# B_PCB1.net
KiCad netlist of a schematic drawn in EAGLE
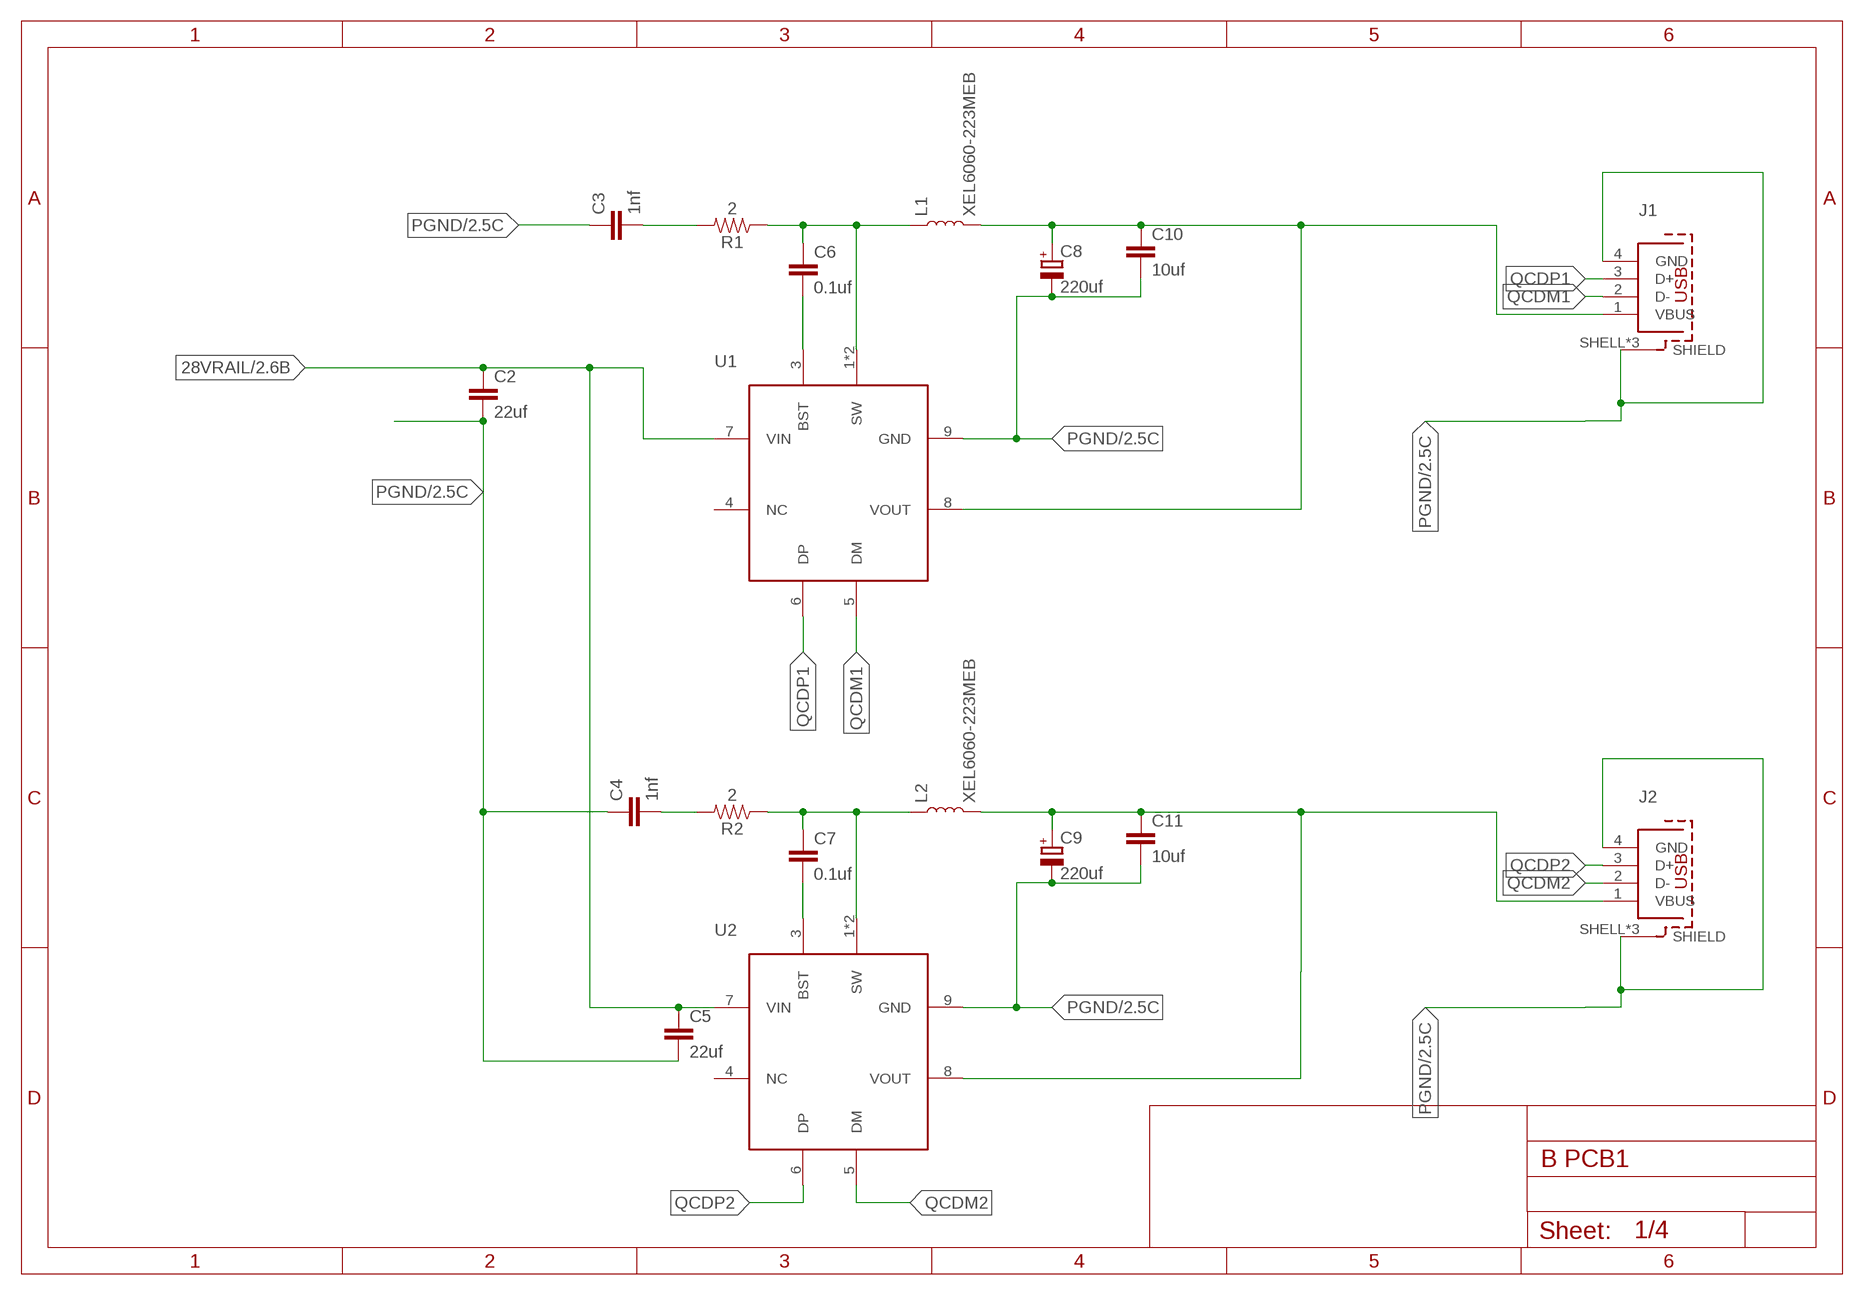
[diagram p0: schematic, sheet 1]
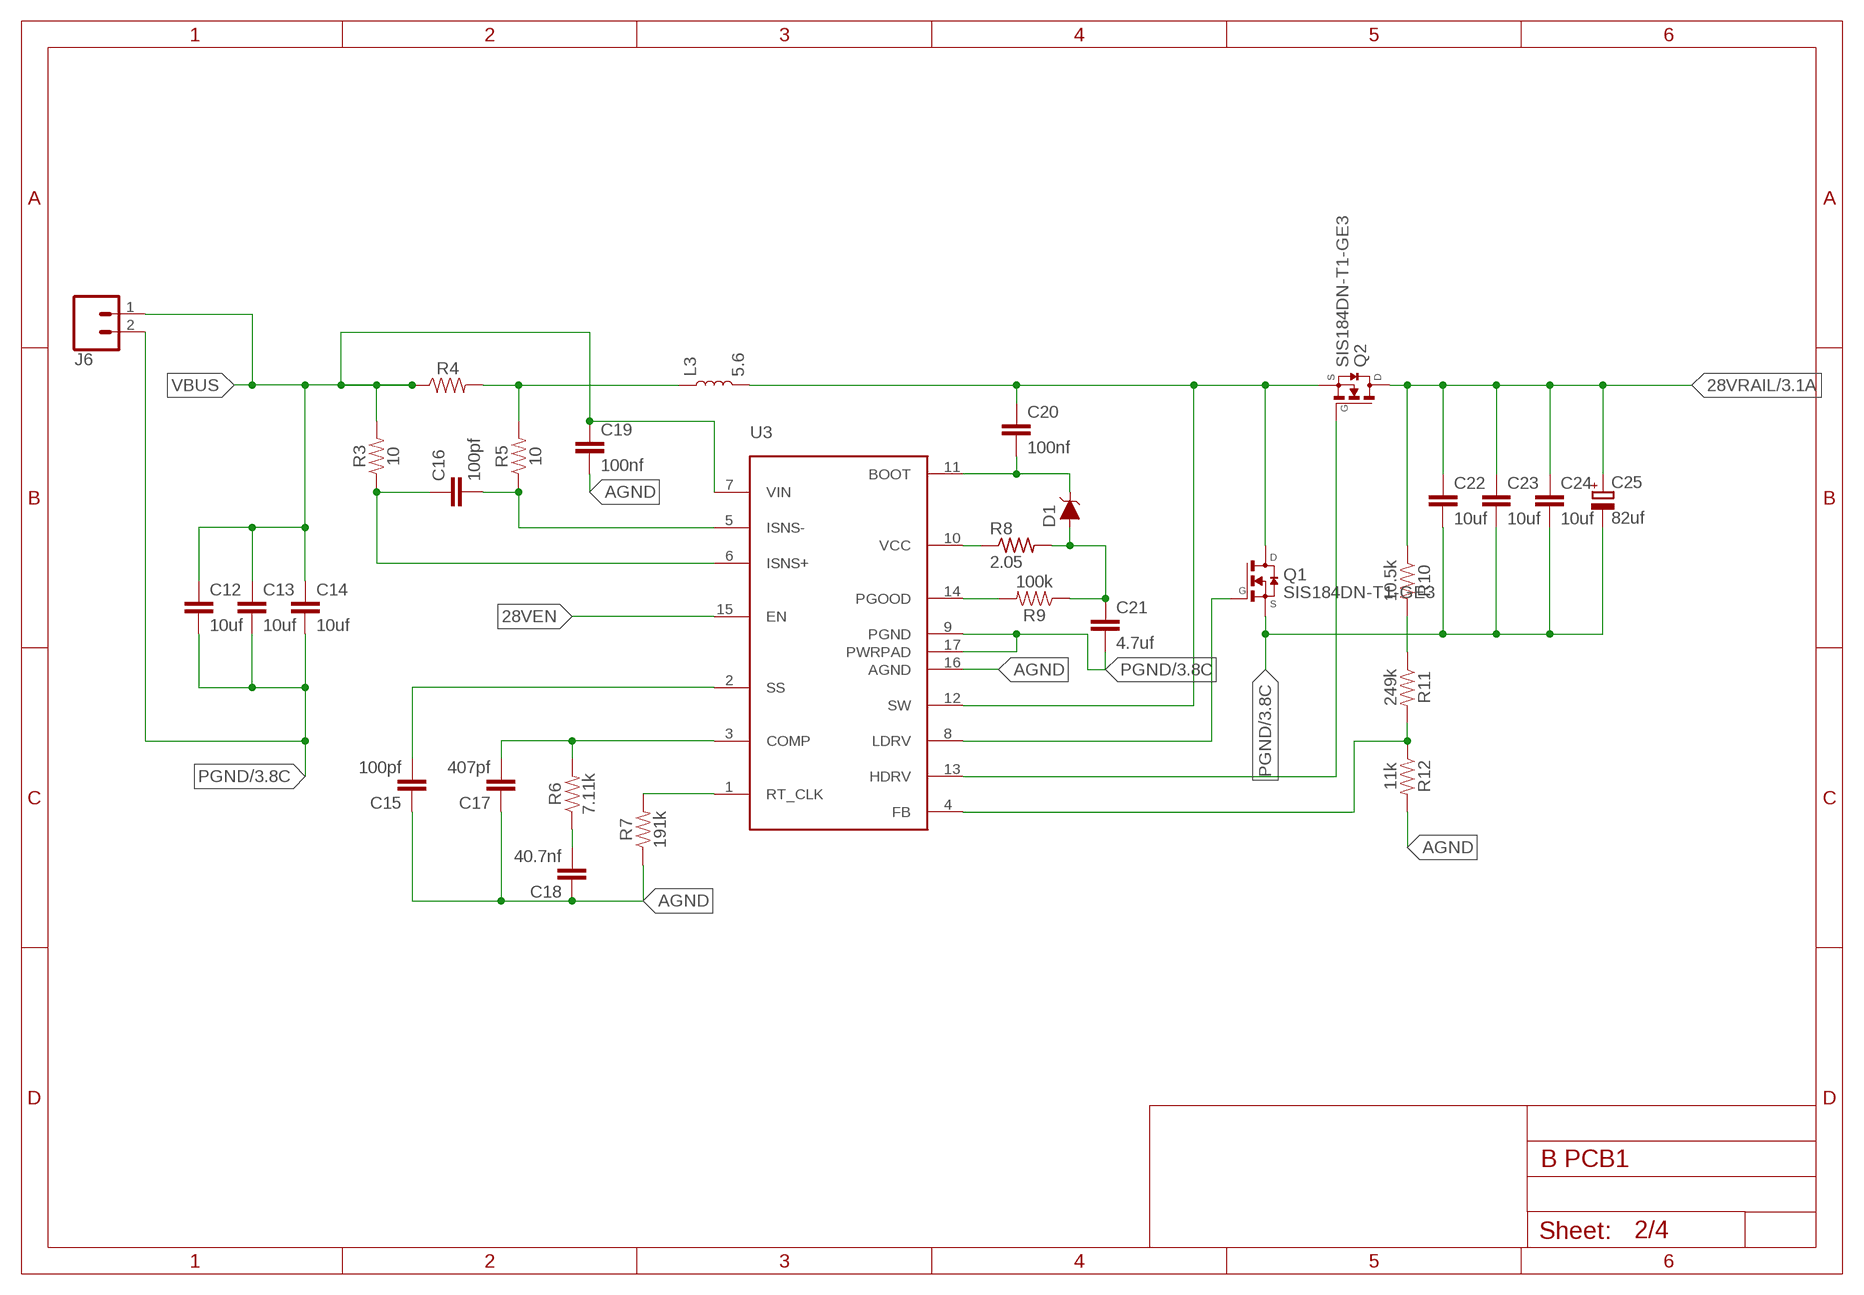
[diagram p1: schematic, sheet 2]
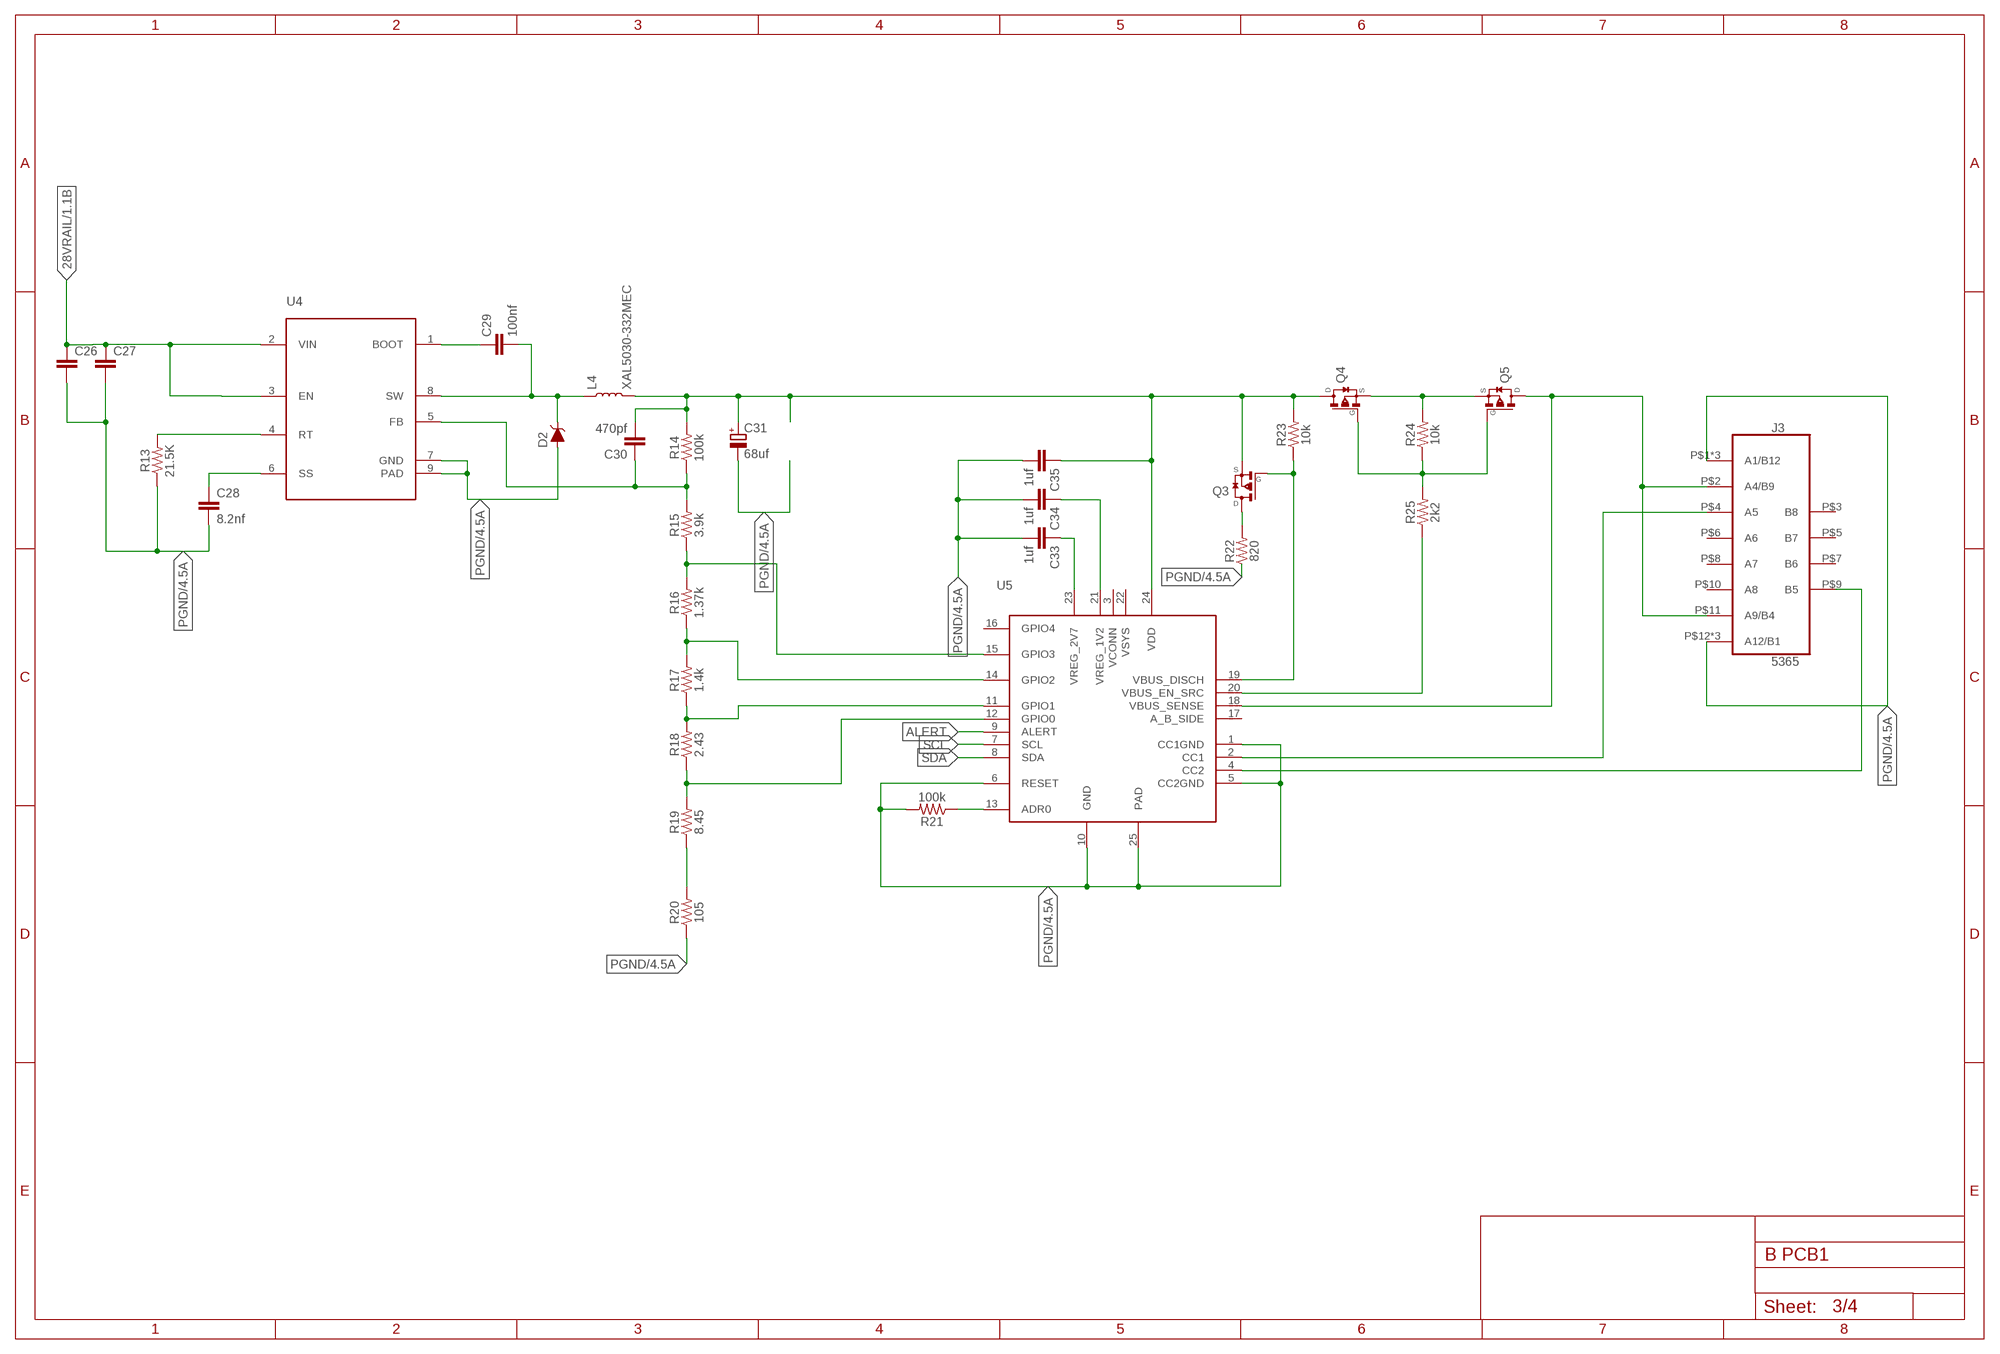
[diagram p2: schematic, sheet 3]
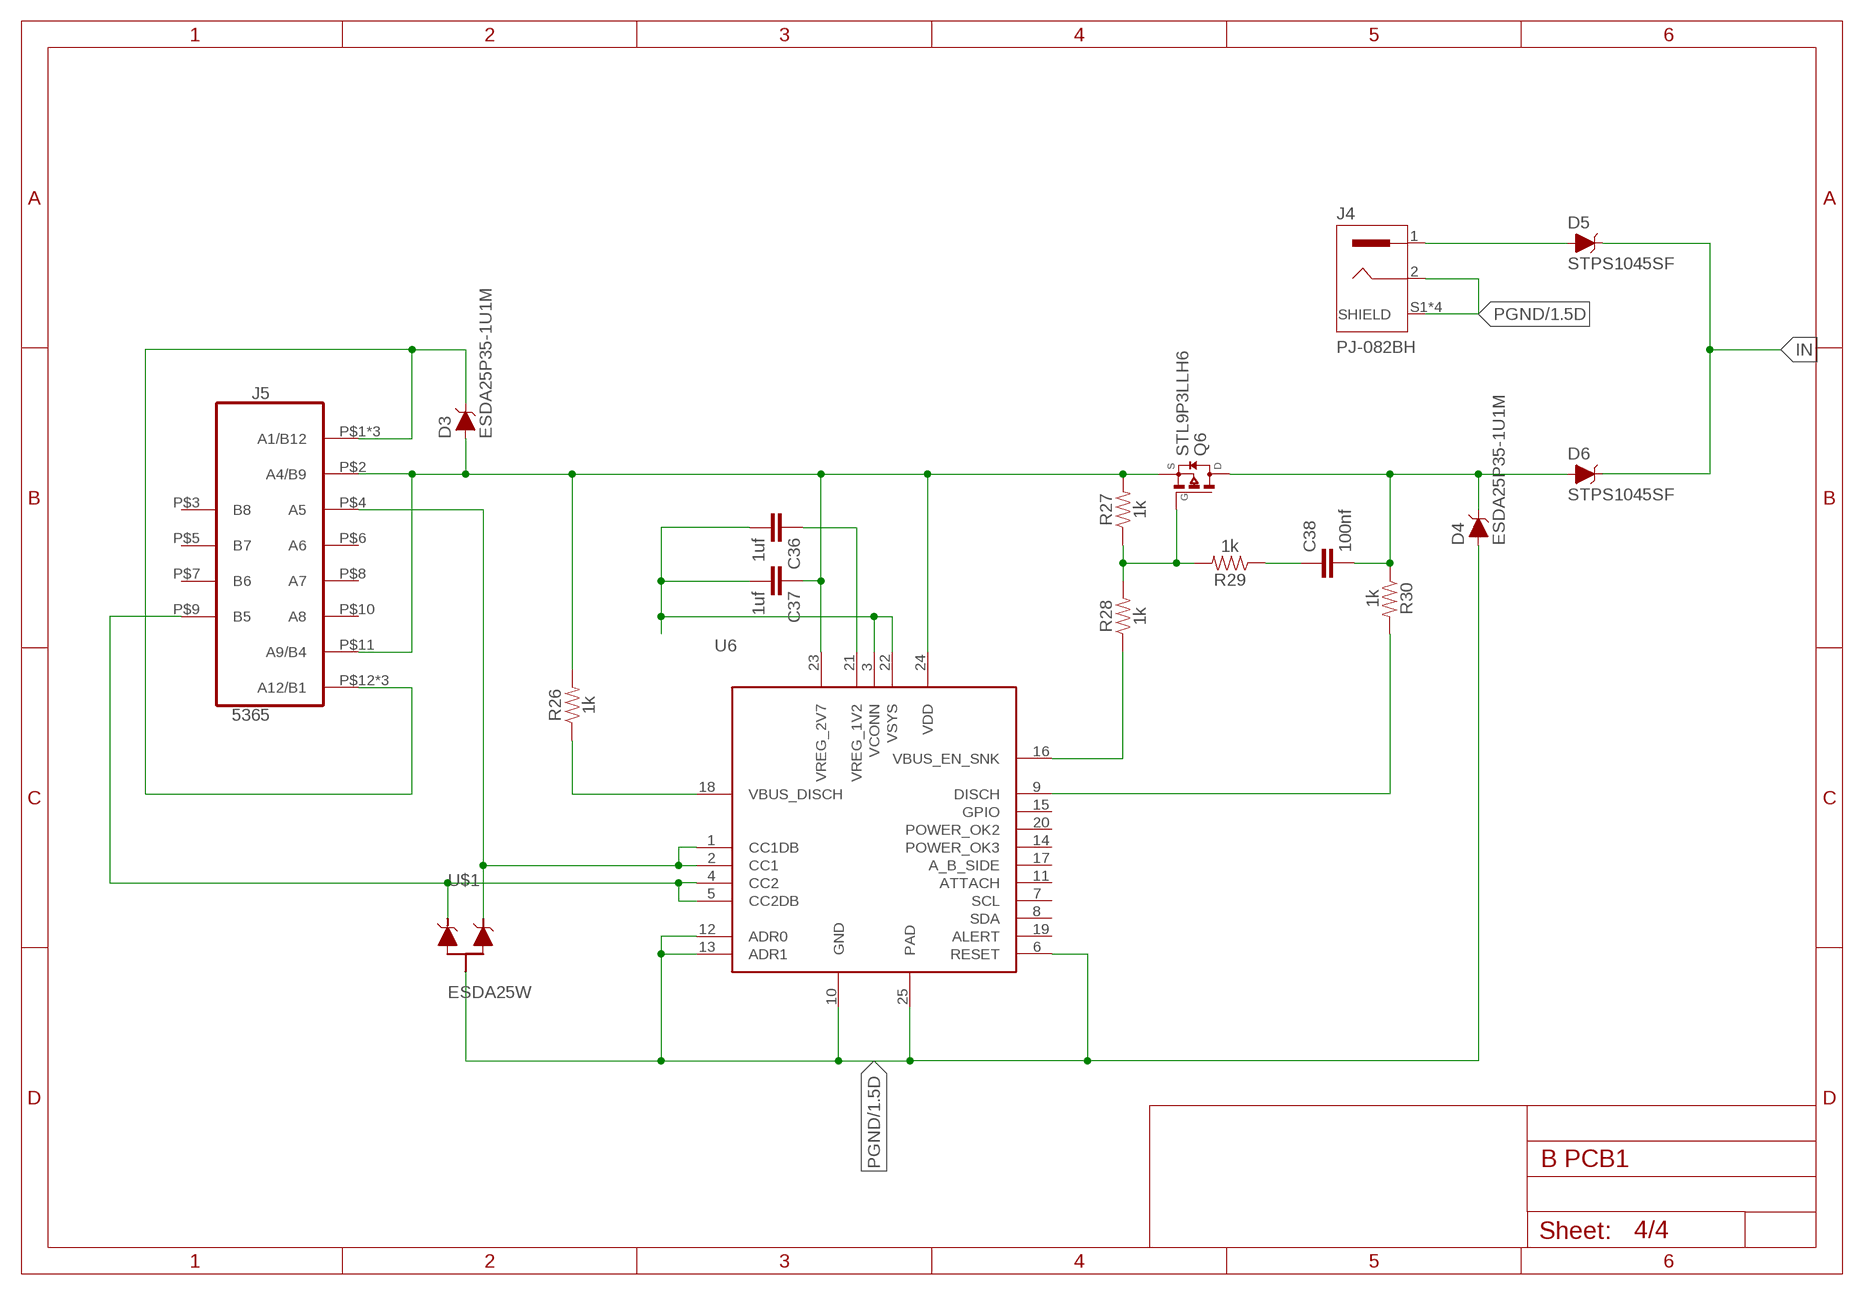
[diagram p3: schematic, sheet 4]

(export (version "E")
  (design (tool "Eeschema 10.0.6"))
  (components
    (comp (ref "C12")
      (value "10uf")
      (footprint "eagle-import:C0805K")
      (libsource (lib "eagle-import") (part "C-EUC0805K"))
    )
    (comp (ref "C13")
      (value "10uf")
      (footprint "eagle-import:C0805K")
      (libsource (lib "eagle-import") (part "C-EUC0805K"))
    )
    (comp (ref "C14")
      (value "10uf")
      (footprint "eagle-import:C0805K")
      (libsource (lib "eagle-import") (part "C-EUC0805K"))
    )
    (comp (ref "C15")
      (value "100pf")
      (footprint "eagle-import:C0402K")
      (libsource (lib "eagle-import") (part "C-EUC0402K"))
    )
    (comp (ref "C16")
      (value "100pf")
      (footprint "eagle-import:C0402K")
      (libsource (lib "eagle-import") (part "C-EUC0402K"))
    )
    (comp (ref "C17")
      (value "407pf")
      (footprint "eagle-import:C0402K")
      (libsource (lib "eagle-import") (part "C-EUC0402K"))
    )
    (comp (ref "C18")
      (value "40.7nf")
      (footprint "eagle-import:C0402K")
      (libsource (lib "eagle-import") (part "C-EUC0402K"))
    )
    (comp (ref "C19")
      (value "100nf")
      (footprint "eagle-import:C0402K")
      (libsource (lib "eagle-import") (part "C-EUC0402K"))
    )
    (comp (ref "C20")
      (value "100nf")
      (footprint "eagle-import:C0402K")
      (libsource (lib "eagle-import") (part "C-EUC0402K"))
    )
    (comp (ref "C21")
      (value "4.7uf")
      (footprint "eagle-import:C0402K")
      (libsource (lib "eagle-import") (part "C-EUC0402K"))
    )
    (comp (ref "C22")
      (value "10uf")
      (footprint "eagle-import:C1206K")
      (libsource (lib "eagle-import") (part "C-EUC1206K"))
    )
    (comp (ref "C23")
      (value "10uf")
      (footprint "eagle-import:C1206K")
      (libsource (lib "eagle-import") (part "C-EUC1206K"))
    )
    (comp (ref "C24")
      (value "10uf")
      (footprint "eagle-import:C1206K")
      (libsource (lib "eagle-import") (part "C-EUC1206K"))
    )
    (comp (ref "C25")
      (value "82uf")
      (footprint "eagle-import:CAPAE660X800")
      (libsource (lib "eagle-import") (part "EMZR250ARA221MF80G"))
    )
    (comp (ref "D1")
      (value "SS24FL")
      (footprint "eagle-import:SODFL3617X108")
      (libsource (lib "eagle-import") (part "SS24FL"))
    )
    (comp (ref "J6")
      (value "CONN_021.4HOLE")
      (footprint "eagle-import:1X02_1.4HOLE")
      (libsource (lib "eagle-import") (part "CONN_021.4HOLE"))
    )
    (comp (ref "L3")
      (value "5.6")
      (footprint "eagle-import:RESM7275X700")
      (libsource (lib "eagle-import") (part "XAL7070-472MEB"))
    )
    (comp (ref "Q1")
      (value "SIS184DN-T1-GE3")
      (footprint "eagle-import:SIS184DN-T1-GE3")
      (libsource (lib "eagle-import") (part "SIS184DN-T1-GE3"))
    )
    (comp (ref "Q2")
      (value "SIS184DN-T1-GE3")
      (footprint "eagle-import:SIS184DN-T1-GE3")
      (libsource (lib "eagle-import") (part "SIS184DN-T1-GE3"))
    )
    (comp (ref "R3")
      (value "10")
      (footprint "eagle-import:0402")
      (libsource (lib "eagle-import") (part "RES4K04020402"))
    )
    (comp (ref "R4")
      (value "LRMAM2512-R0035FT4")
      (footprint "eagle-import:RESC6432X90")
      (libsource (lib "eagle-import") (part "LRMAM2512-R0035FT4"))
    )
    (comp (ref "R5")
      (value "10")
      (footprint "eagle-import:0402")
      (libsource (lib "eagle-import") (part "RES4K04020402"))
    )
    (comp (ref "R6")
      (value "7.11k")
      (footprint "eagle-import:0402")
      (libsource (lib "eagle-import") (part "RES4K04020402"))
    )
    (comp (ref "R7")
      (value "191k")
      (footprint "eagle-import:0402")
      (libsource (lib "eagle-import") (part "RES4K04020402"))
    )
    (comp (ref "R8")
      (value "2.05")
      (footprint "eagle-import:R0603")
      (libsource (lib "eagle-import") (part "R-US_R0603"))
    )
    (comp (ref "R9")
      (value "100k")
      (footprint "eagle-import:0402")
      (libsource (lib "eagle-import") (part "RES4K04020402"))
    )
    (comp (ref "R10")
      (value "10.5k")
      (footprint "eagle-import:0402")
      (libsource (lib "eagle-import") (part "RES4K04020402"))
    )
    (comp (ref "R11")
      (value "249k")
      (footprint "eagle-import:0402")
      (libsource (lib "eagle-import") (part "RES4K04020402"))
    )
    (comp (ref "R12")
      (value "11k")
      (footprint "eagle-import:0402")
      (libsource (lib "eagle-import") (part "RES4K04020402"))
    )
    (comp (ref "U3")
      (value "TPS43061")
      (footprint "eagle-import:QFN50P300X300X100-17T80X120")
      (libsource (lib "eagle-import") (part "TPS43061"))
    )
    (comp (ref "C26")
      (value "C-EUC1210")
      (footprint "eagle-import:C1210")
      (libsource (lib "eagle-import") (part "C-EUC1210"))
    )
    (comp (ref "C27")
      (value "C-EUC1210")
      (footprint "eagle-import:C1210")
      (libsource (lib "eagle-import") (part "C-EUC1210"))
    )
    (comp (ref "C28")
      (value "8.2nf")
      (footprint "eagle-import:C0402K")
      (libsource (lib "eagle-import") (part "C-EUC0402K"))
    )
    (comp (ref "C29")
      (value "100nf")
      (footprint "eagle-import:C0402K")
      (libsource (lib "eagle-import") (part "C-EUC0402K"))
    )
    (comp (ref "C30")
      (value "470pf")
      (footprint "eagle-import:C0402K")
      (libsource (lib "eagle-import") (part "C-EUC0402K"))
    )
    (comp (ref "C31")
      (value "68uf")
      (footprint "eagle-import:CAPAE830X1040")
      (libsource (lib "eagle-import") (part "PCR1H820MCL6GS"))
    )
    (comp (ref "C33")
      (value "1uf")
      (footprint "eagle-import:C0402K")
      (libsource (lib "eagle-import") (part "C-EUC0402K"))
    )
    (comp (ref "C34")
      (value "1uf")
      (footprint "eagle-import:C0402K")
      (libsource (lib "eagle-import") (part "C-EUC0402K"))
    )
    (comp (ref "C35")
      (value "1uf")
      (footprint "eagle-import:C0402K")
      (libsource (lib "eagle-import") (part "C-EUC0402K"))
    )
    (comp (ref "D2")
      (value "B560C-13-F")
      (footprint "eagle-import:DIOM6859X250")
      (libsource (lib "eagle-import") (part "B560C-13-F"))
    )
    (comp (ref "J3")
      (value "5365")
      (footprint "eagle-import:5365")
      (libsource (lib "eagle-import") (part "5365"))
    )
    (comp (ref "L4")
      (value "XAL5030-332MEC")
      (footprint "eagle-import:INDM5355X310")
      (libsource (lib "eagle-import") (part "XAL5030-332MEC"))
    )
    (comp (ref "Q3")
      (value "STR2P3LLH6")
      (footprint "eagle-import:SOT95P280X125-3")
      (libsource (lib "eagle-import") (part "STR2P3LLH6"))
    )
    (comp (ref "Q4")
      (value "STL9P3LLH6")
      (footprint "eagle-import:SON65P330X330X80-8")
      (libsource (lib "eagle-import") (part "STL9P3LLH6"))
    )
    (comp (ref "Q5")
      (value "STL9P3LLH6")
      (footprint "eagle-import:SON65P330X330X80-8")
      (libsource (lib "eagle-import") (part "STL9P3LLH6"))
    )
    (comp (ref "R13")
      (value "21.5K")
      (footprint "eagle-import:0402")
      (libsource (lib "eagle-import") (part "RES4K04020402"))
    )
    (comp (ref "R14")
      (value "100k")
      (footprint "eagle-import:0402")
      (libsource (lib "eagle-import") (part "RES4K04020402"))
    )
    (comp (ref "R15")
      (value "3.9k")
      (footprint "eagle-import:0402")
      (libsource (lib "eagle-import") (part "RES4K04020402"))
    )
    (comp (ref "R16")
      (value "1.37k")
      (footprint "eagle-import:0402")
      (libsource (lib "eagle-import") (part "RES4K04020402"))
    )
    (comp (ref "R17")
      (value "1.4k")
      (footprint "eagle-import:0402")
      (libsource (lib "eagle-import") (part "RES4K04020402"))
    )
    (comp (ref "R18")
      (value "2.43")
      (footprint "eagle-import:0402")
      (libsource (lib "eagle-import") (part "RES4K04020402"))
    )
    (comp (ref "R19")
      (value "8.45")
      (footprint "eagle-import:0402")
      (libsource (lib "eagle-import") (part "RES4K04020402"))
    )
    (comp (ref "R20")
      (value "105")
      (footprint "eagle-import:0402")
      (libsource (lib "eagle-import") (part "RES4K04020402"))
    )
    (comp (ref "R21")
      (value "100k")
      (footprint "eagle-import:0402")
      (fields (field (name "SPICEPREFIX") "R"))
      (libsource (lib "eagle-import") (part "RES4K04020402"))
    )
    (comp (ref "R22")
      (value "820")
      (footprint "eagle-import:0402")
      (libsource (lib "eagle-import") (part "RES4K04020402"))
    )
    (comp (ref "R23")
      (value "10k")
      (footprint "eagle-import:0402")
      (libsource (lib "eagle-import") (part "RES4K04020402"))
    )
    (comp (ref "R24")
      (value "10k")
      (footprint "eagle-import:0402")
      (libsource (lib "eagle-import") (part "RES4K04020402"))
    )
    (comp (ref "R25")
      (value "2k2")
      (footprint "eagle-import:0402")
      (libsource (lib "eagle-import") (part "RES4K04020402"))
    )
    (comp (ref "U4")
      (value "LMR14050")
      (footprint "eagle-import:SOIC127P600X170-9T240X260")
      (libsource (lib "eagle-import") (part "LMR14050"))
    )
    (comp (ref "U5")
      (value "STUSB4700")
      (footprint "eagle-import:QFN50P400X400X100-25T270")
      (libsource (lib "eagle-import") (part "STUSB4700"))
    )
    (comp (ref "C2")
      (value "22uf")
      (footprint "eagle-import:C0805K")
      (libsource (lib "eagle-import") (part "C-EUC0805K"))
    )
    (comp (ref "C3")
      (value "1nf")
      (footprint "eagle-import:C0402K")
      (libsource (lib "eagle-import") (part "C-EUC0402K"))
    )
    (comp (ref "C4")
      (value "1nf")
      (footprint "eagle-import:C0402K")
      (libsource (lib "eagle-import") (part "C-EUC0402K"))
    )
    (comp (ref "C5")
      (value "22uf")
      (footprint "eagle-import:C0805K")
      (libsource (lib "eagle-import") (part "C-EUC0805K"))
    )
    (comp (ref "C6")
      (value "0.1uf")
      (footprint "eagle-import:C0805K")
      (libsource (lib "eagle-import") (part "C-EUC0805K"))
    )
    (comp (ref "C7")
      (value "0.1uf")
      (footprint "eagle-import:C0805K")
      (libsource (lib "eagle-import") (part "C-EUC0805K"))
    )
    (comp (ref "C8")
      (value "220uf")
      (footprint "eagle-import:CAPAE660X800")
      (libsource (lib "eagle-import") (part "EMZR250ARA221MF80G"))
    )
    (comp (ref "C9")
      (value "220uf")
      (footprint "eagle-import:CAPAE660X800")
      (libsource (lib "eagle-import") (part "EMZR250ARA221MF80G"))
    )
    (comp (ref "C10")
      (value "10uf")
      (footprint "eagle-import:C0805K")
      (libsource (lib "eagle-import") (part "C-EUC0805K"))
    )
    (comp (ref "C11")
      (value "10uf")
      (footprint "eagle-import:C0805K")
      (libsource (lib "eagle-import") (part "C-EUC0805K"))
    )
    (comp (ref "J1")
      (value "614004184726")
      (footprint "eagle-import:614004184726")
      (libsource (lib "eagle-import") (part "614004184726"))
    )
    (comp (ref "J2")
      (value "614004184726")
      (footprint "eagle-import:614004184726")
      (libsource (lib "eagle-import") (part "614004184726"))
    )
    (comp (ref "L1")
      (value "XEL6060-223MEB")
      (footprint "eagle-import:RESM6365X610")
      (libsource (lib "eagle-import") (part "XEL6060-222MEB"))
    )
    (comp (ref "L2")
      (value "XEL6060-223MEB")
      (footprint "eagle-import:RESM6365X610")
      (libsource (lib "eagle-import") (part "XEL6060-222MEB"))
    )
    (comp (ref "R1")
      (value "2")
      (footprint "eagle-import:0402")
      (libsource (lib "eagle-import") (part "RES4K04020402"))
    )
    (comp (ref "R2")
      (value "2")
      (footprint "eagle-import:0402")
      (libsource (lib "eagle-import") (part "RES4K04020402"))
    )
    (comp (ref "U1")
      (value "IP6505")
      (footprint "eagle-import:SOIC127P600X165-9T209")
      (libsource (lib "eagle-import") (part "IP6505"))
    )
    (comp (ref "U2")
      (value "IP6505")
      (footprint "eagle-import:SOIC127P600X165-9T209")
      (libsource (lib "eagle-import") (part "IP6505"))
    )
    (comp (ref "C36")
      (value "1uf")
      (footprint "eagle-import:C0402K")
      (libsource (lib "eagle-import") (part "C-EUC0402K"))
    )
    (comp (ref "C37")
      (value "1uf")
      (footprint "eagle-import:C0402K")
      (libsource (lib "eagle-import") (part "C-EUC0402K"))
    )
    (comp (ref "C38")
      (value "100nf")
      (footprint "eagle-import:C0402K")
      (libsource (lib "eagle-import") (part "C-EUC0402K"))
    )
    (comp (ref "D3")
      (value "ESDA25P35-1U1M")
      (footprint "eagle-import:DIODFN160X100X60-2")
      (libsource (lib "eagle-import") (part "ESDA25P35-1U1M"))
    )
    (comp (ref "D4")
      (value "ESDA25P35-1U1M")
      (footprint "eagle-import:DIODFN160X100X60-2")
      (libsource (lib "eagle-import") (part "ESDA25P35-1U1M"))
    )
    (comp (ref "D5")
      (value "STPS1045SF")
      (footprint "eagle-import:DIODFN650X460X120-3")
      (libsource (lib "eagle-import") (part "STPS1045SF"))
    )
    (comp (ref "D6")
      (value "STPS1045SF")
      (footprint "eagle-import:DIODFN650X460X120-3")
      (libsource (lib "eagle-import") (part "STPS1045SF"))
    )
    (comp (ref "J4")
      (value "PJ-082BH")
      (footprint "eagle-import:CUI_PJ-082BH")
      (fields (field (name "MANUFACTURER") "CUI Inc."))
      (libsource (lib "eagle-import") (part "PJ-082BH"))
    )
    (comp (ref "J5")
      (value "5365")
      (footprint "eagle-import:5365")
      (libsource (lib "eagle-import") (part "5365"))
    )
    (comp (ref "Q6")
      (value "STL9P3LLH6")
      (footprint "eagle-import:SON65P330X330X80-8")
      (libsource (lib "eagle-import") (part "STL9P3LLH6"))
    )
    (comp (ref "R26")
      (value "1k")
      (footprint "eagle-import:0402")
      (libsource (lib "eagle-import") (part "RES4K04020402"))
    )
    (comp (ref "R27")
      (value "1k")
      (footprint "eagle-import:0402")
      (libsource (lib "eagle-import") (part "RES4K04020402"))
    )
    (comp (ref "R28")
      (value "1k")
      (footprint "eagle-import:0402")
      (libsource (lib "eagle-import") (part "RES4K04020402"))
    )
    (comp (ref "R29")
      (value "1k")
      (footprint "eagle-import:0402")
      (libsource (lib "eagle-import") (part "RES4K04020402"))
    )
    (comp (ref "R30")
      (value "1k")
      (footprint "eagle-import:0402")
      (libsource (lib "eagle-import") (part "RES4K04020402"))
    )
    (comp (ref "U$1")
      (value "ESDA25W")
      (footprint "eagle-import:SOT65P210X110-3")
      (libsource (lib "eagle-import") (part "ESDA25W"))
    )
    (comp (ref "U6")
      (value "STUSB4500")
      (footprint "eagle-import:QFN50P400X400X100-25T270")
      (libsource (lib "eagle-import") (part "STUSB4500"))
    )
  )
  (nets
    (net (code "1") (name "28VEN") (class "Default")
      (node (ref "U3") (pin "15") (pinfunction "EN_15") (pintype "bidirectional"))
    )
    (net (code "2") (name "28VRAIL") (class "Default")
      (node (ref "C2") (pin "1") (pinfunction "1_1") (pintype "passive"))
      (node (ref "C22") (pin "1") (pinfunction "1_1") (pintype "passive"))
      (node (ref "C23") (pin "1") (pinfunction "1_1") (pintype "passive"))
      (node (ref "C24") (pin "1") (pinfunction "1_1") (pintype "passive"))
      (node (ref "C25") (pin "1") (pinfunction "+_1") (pintype "passive"))
      (node (ref "C26") (pin "1") (pinfunction "1_1") (pintype "passive"))
      (node (ref "C27") (pin "1") (pinfunction "1_1") (pintype "passive"))
      (node (ref "C5") (pin "1") (pinfunction "1_1") (pintype "passive"))
      (node (ref "Q2") (pin "P$5") (pinfunction "D_P$5") (pintype "passive"))
      (node (ref "Q2") (pin "P$6") (pinfunction "D_P$6") (pintype "passive"))
      (node (ref "Q2") (pin "P$7") (pinfunction "D_P$7") (pintype "passive"))
      (node (ref "Q2") (pin "P$8") (pinfunction "D_P$8") (pintype "passive"))
      (node (ref "Q2") (pin "P$9") (pinfunction "D_P$9") (pintype "passive"))
      (node (ref "R10") (pin "1") (pinfunction "1_1") (pintype "passive"))
      (node (ref "U1") (pin "7") (pinfunction "VIN_7") (pintype "bidirectional"))
      (node (ref "U2") (pin "7") (pinfunction "VIN_7") (pintype "bidirectional"))
      (node (ref "U4") (pin "2") (pinfunction "VIN_2") (pintype "bidirectional"))
      (node (ref "U4") (pin "3") (pinfunction "EN_3") (pintype "bidirectional"))
    )
    (net (code "3") (name "AGND") (class "Default")
      (node (ref "C15") (pin "1") (pinfunction "1_1") (pintype "passive"))
      (node (ref "C17") (pin "1") (pinfunction "1_1") (pintype "passive"))
      (node (ref "C18") (pin "1") (pinfunction "1_1") (pintype "passive"))
      (node (ref "C19") (pin "2") (pinfunction "2_2") (pintype "passive"))
      (node (ref "R12") (pin "2") (pinfunction "2_2") (pintype "passive"))
      (node (ref "R7") (pin "1") (pinfunction "1_1") (pintype "passive"))
      (node (ref "U3") (pin "16") (pinfunction "AGND_16") (pintype "bidirectional"))
    )
    (net (code "4") (name "ALERT") (class "Default")
      (node (ref "U5") (pin "9") (pinfunction "ALERT_9") (pintype "bidirectional"))
    )
    (net (code "5") (name "IN") (class "Default")
      (node (ref "D5") (pin "3") (pinfunction "C_3") (pintype "passive"))
      (node (ref "D6") (pin "3") (pinfunction "C_3") (pintype "passive"))
    )
    (net (code "6") (name "Net-(C3-Pad2)") (class "Default")
      (node (ref "C3") (pin "2") (pinfunction "2_2") (pintype "passive"))
      (node (ref "R1") (pin "2") (pinfunction "2_2") (pintype "passive"))
    )
    (net (code "7") (name "Net-(C4-Pad2)") (class "Default")
      (node (ref "C4") (pin "2") (pinfunction "2_2") (pintype "passive"))
      (node (ref "R2") (pin "2") (pinfunction "2_2") (pintype "passive"))
    )
    (net (code "8") (name "Net-(C6-Pad1)") (class "Default")
      (node (ref "C6") (pin "1") (pinfunction "1_1") (pintype "passive"))
      (node (ref "L1") (pin "1") (pinfunction "1_1") (pintype "passive"))
      (node (ref "R1") (pin "1") (pinfunction "1_1") (pintype "passive"))
      (node (ref "U1") (pin "1") (pinfunction "SW_1") (pintype "bidirectional"))
      (node (ref "U1") (pin "2") (pinfunction "SW_2") (pintype "bidirectional"))
    )
    (net (code "9") (name "Net-(C7-Pad1)") (class "Default")
      (node (ref "C7") (pin "1") (pinfunction "1_1") (pintype "passive"))
      (node (ref "L2") (pin "1") (pinfunction "1_1") (pintype "passive"))
      (node (ref "R2") (pin "1") (pinfunction "1_1") (pintype "passive"))
      (node (ref "U2") (pin "1") (pinfunction "SW_1") (pintype "bidirectional"))
      (node (ref "U2") (pin "2") (pinfunction "SW_2") (pintype "bidirectional"))
    )
    (net (code "10") (name "Net-(C8-+)") (class "Default")
      (node (ref "C10") (pin "1") (pinfunction "1_1") (pintype "passive"))
      (node (ref "C8") (pin "1") (pinfunction "+_1") (pintype "passive"))
      (node (ref "J1") (pin "1") (pinfunction "VBUS_1") (pintype "bidirectional"))
      (node (ref "L1") (pin "2") (pinfunction "2_2") (pintype "passive"))
      (node (ref "U1") (pin "8") (pinfunction "VOUT_8") (pintype "bidirectional"))
    )
    (net (code "11") (name "Net-(C9-+)") (class "Default")
      (node (ref "C11") (pin "1") (pinfunction "1_1") (pintype "passive"))
      (node (ref "C9") (pin "1") (pinfunction "+_1") (pintype "passive"))
      (node (ref "J2") (pin "1") (pinfunction "VBUS_1") (pintype "bidirectional"))
      (node (ref "L2") (pin "2") (pinfunction "2_2") (pintype "passive"))
      (node (ref "U2") (pin "8") (pinfunction "VOUT_8") (pintype "bidirectional"))
    )
    (net (code "12") (name "Net-(C18-Pad2)") (class "Default")
      (node (ref "C18") (pin "2") (pinfunction "2_2") (pintype "passive"))
      (node (ref "R6") (pin "1") (pinfunction "1_1") (pintype "passive"))
    )
    (net (code "13") (name "Net-(C31-+)") (class "Default")
      (node (ref "C30") (pin "2") (pinfunction "2_2") (pintype "passive"))
      (node (ref "C31") (pin "1") (pinfunction "+_1") (pintype "passive"))
      (node (ref "C35") (pin "1") (pinfunction "1_1") (pintype "passive"))
      (node (ref "L4") (pin "2") (pinfunction "2_2") (pintype "passive"))
      (node (ref "Q3") (pin "2") (pinfunction "S_2") (pintype "passive"))
      (node (ref "Q4") (pin "5") (pinfunction "D_5") (pintype "passive"))
      (node (ref "Q4") (pin "6") (pinfunction "D_6") (pintype "passive"))
      (node (ref "Q4") (pin "7") (pinfunction "D_7") (pintype "passive"))
      (node (ref "R14") (pin "2") (pinfunction "2_2") (pintype "passive"))
      (node (ref "R23") (pin "2") (pinfunction "2_2") (pintype "passive"))
      (node (ref "U5") (pin "24") (pinfunction "VDD_24") (pintype "bidirectional"))
    )
    (net (code "14") (name "Net-(C38-Pad1)") (class "Default")
      (node (ref "C38") (pin "1") (pinfunction "1_1") (pintype "passive"))
      (node (ref "R29") (pin "1") (pinfunction "1_1") (pintype "passive"))
    )
    (net (code "15") (name "Net-(D1-A)") (class "Default")
      (node (ref "C21") (pin "1") (pinfunction "1_1") (pintype "passive"))
      (node (ref "D1") (pin "2") (pinfunction "A_2") (pintype "passive"))
      (node (ref "R8") (pin "2") (pinfunction "2_2") (pintype "passive"))
      (node (ref "R9") (pin "1") (pinfunction "1_1") (pintype "passive"))
    )
    (net (code "16") (name "Net-(D1-C)") (class "Default")
      (node (ref "C20") (pin "2") (pinfunction "2_2") (pintype "passive"))
      (node (ref "D1") (pin "1") (pinfunction "C_1") (pintype "passive"))
      (node (ref "U3") (pin "11") (pinfunction "BOOT_11") (pintype "bidirectional"))
    )
    (net (code "17") (name "Net-(D2-C)") (class "Default")
      (node (ref "C29") (pin "2") (pinfunction "2_2") (pintype "passive"))
      (node (ref "D2") (pin "1") (pinfunction "C_1") (pintype "passive"))
      (node (ref "L4") (pin "1") (pinfunction "1_1") (pintype "passive"))
      (node (ref "U4") (pin "8") (pinfunction "SW_8") (pintype "bidirectional"))
    )
    (net (code "18") (name "Net-(D3-A)") (class "Default")
      (node (ref "C37") (pin "1") (pinfunction "1_1") (pintype "passive"))
      (node (ref "D3") (pin "2") (pinfunction "A_2") (pintype "passive"))
      (node (ref "J5") (pin "P$11") (pinfunction "A9/B4_P$11") (pintype "bidirectional"))
      (node (ref "J5") (pin "P$2") (pinfunction "A4/B9_P$2") (pintype "bidirectional"))
      (node (ref "Q6") (pin "1") (pinfunction "S_1") (pintype "passive"))
      (node (ref "Q6") (pin "2") (pinfunction "S_2") (pintype "passive"))
      (node (ref "Q6") (pin "3") (pinfunction "S_3") (pintype "passive"))
      (node (ref "R26") (pin "2") (pinfunction "2_2") (pintype "passive"))
      (node (ref "R27") (pin "2") (pinfunction "2_2") (pintype "passive"))
      (node (ref "U6") (pin "23") (pinfunction "VREG_2V7_23") (pintype "bidirectional"))
      (node (ref "U6") (pin "24") (pinfunction "VDD_24") (pintype "bidirectional"))
    )
    (net (code "19") (name "Net-(D3-C)") (class "Default")
      (node (ref "D3") (pin "1") (pinfunction "C_1") (pintype "passive"))
      (node (ref "J5") (pin "P$1") (pinfunction "A1/B12_P$1") (pintype "bidirectional"))
      (node (ref "J5") (pin "P$12") (pinfunction "A12/B1_P$12") (pintype "bidirectional"))
      (node (ref "J5") (pin "P$13") (pinfunction "A1/B12_P$13") (pintype "bidirectional"))
      (node (ref "J5") (pin "P$14") (pinfunction "A12/B1_P$14") (pintype "bidirectional"))
      (node (ref "J5") (pin "P$15") (pinfunction "A1/B12_P$15") (pintype "bidirectional"))
      (node (ref "J5") (pin "P$16") (pinfunction "A12/B1_P$16") (pintype "bidirectional"))
    )
    (net (code "20") (name "Net-(D4-C)") (class "Default")
      (node (ref "C38") (pin "2") (pinfunction "2_2") (pintype "passive"))
      (node (ref "D4") (pin "1") (pinfunction "C_1") (pintype "passive"))
      (node (ref "D6") (pin "1") (pinfunction "A_1") (pintype "passive"))
      (node (ref "D6") (pin "2") (pinfunction "A_2") (pintype "passive"))
      (node (ref "Q6") (pin "5") (pinfunction "D_5") (pintype "passive"))
      (node (ref "Q6") (pin "6") (pinfunction "D_6") (pintype "passive"))
      (node (ref "Q6") (pin "7") (pinfunction "D_7") (pintype "passive"))
      (node (ref "R30") (pin "1") (pinfunction "1_1") (pintype "passive"))
    )
    (net (code "21") (name "Net-(D5-A-Pad1)") (class "Default")
      (node (ref "D5") (pin "1") (pinfunction "A_1") (pintype "passive"))
      (node (ref "D5") (pin "2") (pinfunction "A_2") (pintype "passive"))
      (node (ref "J4") (pin "1") (pinfunction "1_1") (pintype "passive"))
    )
    (net (code "22") (name "Net-(J3-A4{slash}B9)") (class "Default")
      (node (ref "J3") (pin "P$11") (pinfunction "A9/B4_P$11") (pintype "bidirectional"))
      (node (ref "J3") (pin "P$2") (pinfunction "A4/B9_P$2") (pintype "bidirectional"))
      (node (ref "Q5") (pin "5") (pinfunction "D_5") (pintype "passive"))
      (node (ref "Q5") (pin "6") (pinfunction "D_6") (pintype "passive"))
      (node (ref "Q5") (pin "7") (pinfunction "D_7") (pintype "passive"))
      (node (ref "U5") (pin "18") (pinfunction "VBUS_SENSE_18") (pintype "bidirectional"))
    )
    (net (code "23") (name "Net-(J3-A5)") (class "Default")
      (node (ref "J3") (pin "P$4") (pinfunction "A5_P$4") (pintype "bidirectional"))
      (node (ref "U5") (pin "2") (pinfunction "CC1_2") (pintype "bidirectional"))
    )
    (net (code "24") (name "Net-(J3-B5)") (class "Default")
      (node (ref "J3") (pin "P$9") (pinfunction "B5_P$9") (pintype "bidirectional"))
      (node (ref "U5") (pin "4") (pinfunction "CC2_4") (pintype "bidirectional"))
    )
    (net (code "25") (name "Net-(J5-A5)") (class "Default")
      (node (ref "J5") (pin "P$4") (pinfunction "A5_P$4") (pintype "bidirectional"))
      (node (ref "U$1") (pin "2") (pinfunction "C2_2") (pintype "passive"))
      (node (ref "U6") (pin "1") (pinfunction "CC1DB_1") (pintype "bidirectional"))
      (node (ref "U6") (pin "2") (pinfunction "CC1_2") (pintype "bidirectional"))
    )
    (net (code "26") (name "Net-(J5-B5)") (class "Default")
      (node (ref "J5") (pin "P$9") (pinfunction "B5_P$9") (pintype "bidirectional"))
      (node (ref "U$1") (pin "1") (pinfunction "C1_1") (pintype "passive"))
      (node (ref "U6") (pin "4") (pinfunction "CC2_4") (pintype "bidirectional"))
      (node (ref "U6") (pin "5") (pinfunction "CC2DB_5") (pintype "bidirectional"))
    )
    (net (code "27") (name "Net-(L3-Pad1)") (class "Default")
      (node (ref "L3") (pin "1") (pinfunction "1_1") (pintype "passive"))
      (node (ref "R4") (pin "2") (pinfunction "2_2") (pintype "passive"))
      (node (ref "R5") (pin "2") (pinfunction "2_2") (pintype "passive"))
    )
    (net (code "28") (name "Net-(Q1-G)") (class "Default")
      (node (ref "Q1") (pin "P$4") (pinfunction "G_P$4") (pintype "passive"))
      (node (ref "U3") (pin "8") (pinfunction "LDRV_8") (pintype "bidirectional"))
    )
    (net (code "29") (name "Net-(Q2-G)") (class "Default")
      (node (ref "Q2") (pin "P$4") (pinfunction "G_P$4") (pintype "passive"))
      (node (ref "U3") (pin "13") (pinfunction "HDRV_13") (pintype "bidirectional"))
    )
    (net (code "30") (name "Net-(Q3-D)") (class "Default")
      (node (ref "Q3") (pin "3") (pinfunction "D_3") (pintype "passive"))
      (node (ref "R22") (pin "2") (pinfunction "2_2") (pintype "passive"))
    )
    (net (code "31") (name "Net-(Q3-G)") (class "Default")
      (node (ref "Q3") (pin "1") (pinfunction "G_1") (pintype "passive"))
      (node (ref "R23") (pin "1") (pinfunction "1_1") (pintype "passive"))
      (node (ref "U5") (pin "19") (pinfunction "VBUS_DISCH_19") (pintype "bidirectional"))
    )
    (net (code "32") (name "Net-(Q4-G)") (class "Default")
      (node (ref "Q4") (pin "4") (pinfunction "G_4") (pintype "passive"))
      (node (ref "Q5") (pin "4") (pinfunction "G_4") (pintype "passive"))
      (node (ref "R24") (pin "1") (pinfunction "1_1") (pintype "passive"))
      (node (ref "R25") (pin "2") (pinfunction "2_2") (pintype "passive"))
    )
    (net (code "33") (name "Net-(Q4-S-Pad1)") (class "Default")
      (node (ref "Q4") (pin "1") (pinfunction "S_1") (pintype "passive"))
      (node (ref "Q4") (pin "2") (pinfunction "S_2") (pintype "passive"))
      (node (ref "Q4") (pin "3") (pinfunction "S_3") (pintype "passive"))
      (node (ref "Q5") (pin "1") (pinfunction "S_1") (pintype "passive"))
      (node (ref "Q5") (pin "2") (pinfunction "S_2") (pintype "passive"))
      (node (ref "Q5") (pin "3") (pinfunction "S_3") (pintype "passive"))
      (node (ref "R24") (pin "2") (pinfunction "2_2") (pintype "passive"))
    )
    (net (code "34") (name "Net-(Q6-G)") (class "Default")
      (node (ref "Q6") (pin "4") (pinfunction "G_4") (pintype "passive"))
      (node (ref "R27") (pin "1") (pinfunction "1_1") (pintype "passive"))
      (node (ref "R28") (pin "2") (pinfunction "2_2") (pintype "passive"))
      (node (ref "R29") (pin "2") (pinfunction "2_2") (pintype "passive"))
    )
    (net (code "35") (name "Net-(R10-Pad2)") (class "Default")
      (node (ref "R10") (pin "2") (pinfunction "2_2") (pintype "passive"))
      (node (ref "R11") (pin "1") (pinfunction "1_1") (pintype "passive"))
    )
    (net (code "36") (name "Net-(R19-Pad1)") (class "Default")
      (node (ref "R19") (pin "1") (pinfunction "1_1") (pintype "passive"))
      (node (ref "R20") (pin "2") (pinfunction "2_2") (pintype "passive"))
    )
    (net (code "37") (name "Net-(U1-BST)") (class "Default")
      (node (ref "C6") (pin "2") (pinfunction "2_2") (pintype "passive"))
      (node (ref "U1") (pin "3") (pinfunction "BST_3") (pintype "bidirectional"))
    )
    (net (code "38") (name "Net-(U2-BST)") (class "Default")
      (node (ref "C7") (pin "2") (pinfunction "2_2") (pintype "passive"))
      (node (ref "U2") (pin "3") (pinfunction "BST_3") (pintype "bidirectional"))
    )
    (net (code "39") (name "Net-(U3-COMP)") (class "Default")
      (node (ref "C17") (pin "2") (pinfunction "2_2") (pintype "passive"))
      (node (ref "R6") (pin "2") (pinfunction "2_2") (pintype "passive"))
      (node (ref "U3") (pin "3") (pinfunction "COMP_3") (pintype "bidirectional"))
    )
    (net (code "40") (name "Net-(U3-FB)") (class "Default")
      (node (ref "R11") (pin "2") (pinfunction "2_2") (pintype "passive"))
      (node (ref "R12") (pin "1") (pinfunction "1_1") (pintype "passive"))
      (node (ref "U3") (pin "4") (pinfunction "FB_4") (pintype "bidirectional"))
    )
    (net (code "41") (name "Net-(U3-ISNS+)") (class "Default")
      (node (ref "C16") (pin "1") (pinfunction "1_1") (pintype "passive"))
      (node (ref "R3") (pin "1") (pinfunction "1_1") (pintype "passive"))
      (node (ref "U3") (pin "6") (pinfunction "ISNS+_6") (pintype "bidirectional"))
    )
    (net (code "42") (name "Net-(U3-ISNS-)") (class "Default")
      (node (ref "C16") (pin "2") (pinfunction "2_2") (pintype "passive"))
      (node (ref "R5") (pin "1") (pinfunction "1_1") (pintype "passive"))
      (node (ref "U3") (pin "5") (pinfunction "ISNS-_5") (pintype "bidirectional"))
    )
    (net (code "43") (name "Net-(U3-PGOOD)") (class "Default")
      (node (ref "R9") (pin "2") (pinfunction "2_2") (pintype "passive"))
      (node (ref "U3") (pin "14") (pinfunction "PGOOD_14") (pintype "bidirectional"))
    )
    (net (code "44") (name "Net-(U3-RT_CLK)") (class "Default")
      (node (ref "R7") (pin "2") (pinfunction "2_2") (pintype "passive"))
      (node (ref "U3") (pin "1") (pinfunction "RT_CLK_1") (pintype "bidirectional"))
    )
    (net (code "45") (name "Net-(U3-SS)") (class "Default")
      (node (ref "C15") (pin "2") (pinfunction "2_2") (pintype "passive"))
      (node (ref "U3") (pin "2") (pinfunction "SS_2") (pintype "bidirectional"))
    )
    (net (code "46") (name "Net-(U3-SW)") (class "Default")
      (node (ref "C20") (pin "1") (pinfunction "1_1") (pintype "passive"))
      (node (ref "L3") (pin "2") (pinfunction "2_2") (pintype "passive"))
      (node (ref "Q1") (pin "P$5") (pinfunction "D_P$5") (pintype "passive"))
      (node (ref "Q1") (pin "P$6") (pinfunction "D_P$6") (pintype "passive"))
      (node (ref "Q1") (pin "P$7") (pinfunction "D_P$7") (pintype "passive"))
      (node (ref "Q1") (pin "P$8") (pinfunction "D_P$8") (pintype "passive"))
      (node (ref "Q1") (pin "P$9") (pinfunction "D_P$9") (pintype "passive"))
      (node (ref "Q2") (pin "P$1") (pinfunction "S_P$1") (pintype "passive"))
      (node (ref "Q2") (pin "P$2") (pinfunction "S_P$2") (pintype "passive"))
      (node (ref "Q2") (pin "P$3") (pinfunction "S_P$3") (pintype "passive"))
      (node (ref "U3") (pin "12") (pinfunction "SW_12") (pintype "bidirectional"))
    )
    (net (code "47") (name "Net-(U3-VCC)") (class "Default")
      (node (ref "R8") (pin "1") (pinfunction "1_1") (pintype "passive"))
      (node (ref "U3") (pin "10") (pinfunction "VCC_10") (pintype "bidirectional"))
    )
    (net (code "48") (name "Net-(U4-BOOT)") (class "Default")
      (node (ref "C29") (pin "1") (pinfunction "1_1") (pintype "passive"))
      (node (ref "U4") (pin "1") (pinfunction "BOOT_1") (pintype "bidirectional"))
    )
    (net (code "49") (name "Net-(U4-FB)") (class "Default")
      (node (ref "C30") (pin "1") (pinfunction "1_1") (pintype "passive"))
      (node (ref "R14") (pin "1") (pinfunction "1_1") (pintype "passive"))
      (node (ref "R15") (pin "2") (pinfunction "2_2") (pintype "passive"))
      (node (ref "U4") (pin "5") (pinfunction "FB_5") (pintype "bidirectional"))
    )
    (net (code "50") (name "Net-(U4-RT)") (class "Default")
      (node (ref "R13") (pin "2") (pinfunction "2_2") (pintype "passive"))
      (node (ref "U4") (pin "4") (pinfunction "RT_4") (pintype "bidirectional"))
    )
    (net (code "51") (name "Net-(U4-SS)") (class "Default")
      (node (ref "C28") (pin "1") (pinfunction "1_1") (pintype "passive"))
      (node (ref "U4") (pin "6") (pinfunction "SS_6") (pintype "bidirectional"))
    )
    (net (code "52") (name "Net-(U5-ADR0)") (class "Default")
      (node (ref "R21") (pin "1") (pinfunction "1_1") (pintype "passive"))
      (node (ref "U5") (pin "13") (pinfunction "ADR0_13") (pintype "bidirectional"))
    )
    (net (code "53") (name "Net-(U5-GPIO0)") (class "Default")
      (node (ref "R18") (pin "1") (pinfunction "1_1") (pintype "passive"))
      (node (ref "R19") (pin "2") (pinfunction "2_2") (pintype "passive"))
      (node (ref "U5") (pin "12") (pinfunction "GPIO0_12") (pintype "bidirectional"))
    )
    (net (code "54") (name "Net-(U5-GPIO1)") (class "Default")
      (node (ref "R17") (pin "1") (pinfunction "1_1") (pintype "passive"))
      (node (ref "R18") (pin "2") (pinfunction "2_2") (pintype "passive"))
      (node (ref "U5") (pin "11") (pinfunction "GPIO1_11") (pintype "bidirectional"))
    )
    (net (code "55") (name "Net-(U5-GPIO2)") (class "Default")
      (node (ref "R16") (pin "1") (pinfunction "1_1") (pintype "passive"))
      (node (ref "R17") (pin "2") (pinfunction "2_2") (pintype "passive"))
      (node (ref "U5") (pin "14") (pinfunction "GPIO2_14") (pintype "bidirectional"))
    )
    (net (code "56") (name "Net-(U5-GPIO3)") (class "Default")
      (node (ref "R15") (pin "1") (pinfunction "1_1") (pintype "passive"))
      (node (ref "R16") (pin "2") (pinfunction "2_2") (pintype "passive"))
      (node (ref "U5") (pin "15") (pinfunction "GPIO3_15") (pintype "bidirectional"))
    )
    (net (code "57") (name "Net-(U5-VBUS_EN_SRC)") (class "Default")
      (node (ref "R25") (pin "1") (pinfunction "1_1") (pintype "passive"))
      (node (ref "U5") (pin "20") (pinfunction "VBUS_EN_SRC_20") (pintype "bidirectional"))
    )
    (net (code "58") (name "Net-(U5-VREG_1V2)") (class "Default")
      (node (ref "C34") (pin "1") (pinfunction "1_1") (pintype "passive"))
      (node (ref "U5") (pin "21") (pinfunction "VREG_1V2_21") (pintype "bidirectional"))
    )
    (net (code "59") (name "Net-(U5-VREG_2V7)") (class "Default")
      (node (ref "C33") (pin "1") (pinfunction "1_1") (pintype "passive"))
      (node (ref "U5") (pin "23") (pinfunction "VREG_2V7_23") (pintype "bidirectional"))
    )
    (net (code "60") (name "Net-(U6-DISCH)") (class "Default")
      (node (ref "R30") (pin "2") (pinfunction "2_2") (pintype "passive"))
      (node (ref "U6") (pin "9") (pinfunction "DISCH_9") (pintype "bidirectional"))
    )
    (net (code "61") (name "Net-(U6-VBUS_DISCH)") (class "Default")
      (node (ref "R26") (pin "1") (pinfunction "1_1") (pintype "passive"))
      (node (ref "U6") (pin "18") (pinfunction "VBUS_DISCH_18") (pintype "bidirectional"))
    )
    (net (code "62") (name "Net-(U6-VBUS_EN_SNK)") (class "Default")
      (node (ref "R28") (pin "1") (pinfunction "1_1") (pintype "passive"))
      (node (ref "U6") (pin "16") (pinfunction "VBUS_EN_SNK_16") (pintype "bidirectional"))
    )
    (net (code "63") (name "Net-(U6-VCONN)") (class "Default")
      (node (ref "C36") (pin "2") (pinfunction "2_2") (pintype "passive"))
      (node (ref "C37") (pin "2") (pinfunction "2_2") (pintype "passive"))
      (node (ref "U6") (pin "22") (pinfunction "VSYS_22") (pintype "bidirectional"))
      (node (ref "U6") (pin "3") (pinfunction "VCONN_3") (pintype "bidirectional"))
    )
    (net (code "64") (name "Net-(U6-VREG_1V2)") (class "Default")
      (node (ref "C36") (pin "1") (pinfunction "1_1") (pintype "passive"))
      (node (ref "U6") (pin "21") (pinfunction "VREG_1V2_21") (pintype "bidirectional"))
    )
    (net (code "65") (name "PGND") (class "Default")
      (node (ref "C10") (pin "2") (pinfunction "2_2") (pintype "passive"))
      (node (ref "C11") (pin "2") (pinfunction "2_2") (pintype "passive"))
      (node (ref "C12") (pin "2") (pinfunction "2_2") (pintype "passive"))
      (node (ref "C13") (pin "2") (pinfunction "2_2") (pintype "passive"))
      (node (ref "C14") (pin "2") (pinfunction "2_2") (pintype "passive"))
      (node (ref "C2") (pin "2") (pinfunction "2_2") (pintype "passive"))
      (node (ref "C21") (pin "2") (pinfunction "2_2") (pintype "passive"))
      (node (ref "C22") (pin "2") (pinfunction "2_2") (pintype "passive"))
      (node (ref "C23") (pin "2") (pinfunction "2_2") (pintype "passive"))
      (node (ref "C24") (pin "2") (pinfunction "2_2") (pintype "passive"))
      (node (ref "C25") (pin "2") (pinfunction "-_2") (pintype "passive"))
      (node (ref "C26") (pin "2") (pinfunction "2_2") (pintype "passive"))
      (node (ref "C27") (pin "2") (pinfunction "2_2") (pintype "passive"))
      (node (ref "C28") (pin "2") (pinfunction "2_2") (pintype "passive"))
      (node (ref "C3") (pin "1") (pinfunction "1_1") (pintype "passive"))
      (node (ref "C31") (pin "2") (pinfunction "-_2") (pintype "passive"))
      (node (ref "C33") (pin "2") (pinfunction "2_2") (pintype "passive"))
      (node (ref "C34") (pin "2") (pinfunction "2_2") (pintype "passive"))
      (node (ref "C35") (pin "2") (pinfunction "2_2") (pintype "passive"))
      (node (ref "C4") (pin "1") (pinfunction "1_1") (pintype "passive"))
      (node (ref "C5") (pin "2") (pinfunction "2_2") (pintype "passive"))
      (node (ref "C8") (pin "2") (pinfunction "-_2") (pintype "passive"))
      (node (ref "C9") (pin "2") (pinfunction "-_2") (pintype "passive"))
      (node (ref "D2") (pin "2") (pinfunction "A_2") (pintype "passive"))
      (node (ref "D4") (pin "2") (pinfunction "A_2") (pintype "passive"))
      (node (ref "J1") (pin "4") (pinfunction "GND_4") (pintype "bidirectional"))
      (node (ref "J1") (pin "SHELL") (pinfunction "SHIELD_SHELL") (pintype "bidirectional"))
      (node (ref "J1") (pin "SHELL1") (pinfunction "SHIELD_SHELL1") (pintype "bidirectional"))
      (node (ref "J1") (pin "SHELL2") (pinfunction "SHIELD_SHELL2") (pintype "bidirectional"))
      (node (ref "J2") (pin "4") (pinfunction "GND_4") (pintype "bidirectional"))
      (node (ref "J2") (pin "SHELL") (pinfunction "SHIELD_SHELL") (pintype "bidirectional"))
      (node (ref "J2") (pin "SHELL1") (pinfunction "SHIELD_SHELL1") (pintype "bidirectional"))
      (node (ref "J2") (pin "SHELL2") (pinfunction "SHIELD_SHELL2") (pintype "bidirectional"))
      (node (ref "J3") (pin "P$1") (pinfunction "A1/B12_P$1") (pintype "bidirectional"))
      (node (ref "J3") (pin "P$12") (pinfunction "A12/B1_P$12") (pintype "bidirectional"))
      (node (ref "J3") (pin "P$13") (pinfunction "A1/B12_P$13") (pintype "bidirectional"))
      (node (ref "J3") (pin "P$14") (pinfunction "A12/B1_P$14") (pintype "bidirectional"))
      (node (ref "J3") (pin "P$15") (pinfunction "A1/B12_P$15") (pintype "bidirectional"))
      (node (ref "J3") (pin "P$16") (pinfunction "A12/B1_P$16") (pintype "bidirectional"))
      (node (ref "J4") (pin "2") (pinfunction "2_2") (pintype "passive"))
      (node (ref "J4") (pin "S1") (pinfunction "SHIELD_S1") (pintype "passive"))
      (node (ref "J4") (pin "S2") (pinfunction "SHIELD_S2") (pintype "passive"))
      (node (ref "J4") (pin "S3") (pinfunction "SHIELD_S3") (pintype "passive"))
      (node (ref "J4") (pin "S4") (pinfunction "SHIELD_S4") (pintype "passive"))
      (node (ref "J6") (pin "2") (pinfunction "2_2") (pintype "passive"))
      (node (ref "Q1") (pin "P$1") (pinfunction "S_P$1") (pintype "passive"))
      (node (ref "Q1") (pin "P$2") (pinfunction "S_P$2") (pintype "passive"))
      (node (ref "Q1") (pin "P$3") (pinfunction "S_P$3") (pintype "passive"))
      (node (ref "R13") (pin "1") (pinfunction "1_1") (pintype "passive"))
      (node (ref "R20") (pin "1") (pinfunction "1_1") (pintype "passive"))
      (node (ref "R21") (pin "2") (pinfunction "2_2") (pintype "passive"))
      (node (ref "R22") (pin "1") (pinfunction "1_1") (pintype "passive"))
      (node (ref "U$1") (pin "3") (pinfunction "A_3") (pintype "passive"))
      (node (ref "U1") (pin "9") (pinfunction "GND_9") (pintype "bidirectional"))
      (node (ref "U2") (pin "9") (pinfunction "GND_9") (pintype "bidirectional"))
      (node (ref "U3") (pin "17") (pinfunction "PWRPAD_17") (pintype "bidirectional"))
      (node (ref "U3") (pin "9") (pinfunction "PGND_9") (pintype "bidirectional"))
      (node (ref "U4") (pin "7") (pinfunction "GND_7") (pintype "bidirectional"))
      (node (ref "U4") (pin "9") (pinfunction "PAD_9") (pintype "bidirectional"))
      (node (ref "U5") (pin "1") (pinfunction "CC1GND_1") (pintype "bidirectional"))
      (node (ref "U5") (pin "10") (pinfunction "GND_10") (pintype "bidirectional"))
      (node (ref "U5") (pin "25") (pinfunction "PAD_25") (pintype "bidirectional"))
      (node (ref "U5") (pin "5") (pinfunction "CC2GND_5") (pintype "bidirectional"))
      (node (ref "U5") (pin "6") (pinfunction "RESET_6") (pintype "bidirectional"))
      (node (ref "U6") (pin "10") (pinfunction "GND_10") (pintype "bidirectional"))
      (node (ref "U6") (pin "12") (pinfunction "ADR0_12") (pintype "bidirectional"))
      (node (ref "U6") (pin "13") (pinfunction "ADR1_13") (pintype "bidirectional"))
      (node (ref "U6") (pin "25") (pinfunction "PAD_25") (pintype "bidirectional"))
      (node (ref "U6") (pin "6") (pinfunction "RESET_6") (pintype "bidirectional"))
    )
    (net (code "66") (name "QCDM1") (class "Default")
      (node (ref "J1") (pin "2") (pinfunction "D-_2") (pintype "bidirectional"))
      (node (ref "U1") (pin "5") (pinfunction "DM_5") (pintype "bidirectional"))
    )
    (net (code "67") (name "QCDM2") (class "Default")
      (node (ref "J2") (pin "2") (pinfunction "D-_2") (pintype "bidirectional"))
      (node (ref "U2") (pin "5") (pinfunction "DM_5") (pintype "bidirectional"))
    )
    (net (code "68") (name "QCDP1") (class "Default")
      (node (ref "J1") (pin "3") (pinfunction "D+_3") (pintype "bidirectional"))
      (node (ref "U1") (pin "6") (pinfunction "DP_6") (pintype "bidirectional"))
    )
    (net (code "69") (name "QCDP2") (class "Default")
      (node (ref "J2") (pin "3") (pinfunction "D+_3") (pintype "bidirectional"))
      (node (ref "U2") (pin "6") (pinfunction "DP_6") (pintype "bidirectional"))
    )
    (net (code "70") (name "SCL") (class "Default")
      (node (ref "U5") (pin "7") (pinfunction "SCL_7") (pintype "bidirectional"))
    )
    (net (code "71") (name "SDA") (class "Default")
      (node (ref "U5") (pin "8") (pinfunction "SDA_8") (pintype "bidirectional"))
    )
    (net (code "72") (name "VBUS") (class "Default")
      (node (ref "C12") (pin "1") (pinfunction "1_1") (pintype "passive"))
      (node (ref "C13") (pin "1") (pinfunction "1_1") (pintype "passive"))
      (node (ref "C14") (pin "1") (pinfunction "1_1") (pintype "passive"))
      (node (ref "C19") (pin "1") (pinfunction "1_1") (pintype "passive"))
      (node (ref "J6") (pin "1") (pinfunction "1_1") (pintype "passive"))
      (node (ref "R3") (pin "2") (pinfunction "2_2") (pintype "passive"))
      (node (ref "R4") (pin "1") (pinfunction "1_1") (pintype "passive"))
      (node (ref "U3") (pin "7") (pinfunction "VIN_7") (pintype "bidirectional"))
    )
    (net (code "73") (name "unconnected-(J3-A6-PadP$6)") (class "Default")
      (node (ref "J3") (pin "P$6") (pinfunction "A6_P$6") (pintype "bidirectional"))
    )
    (net (code "74") (name "unconnected-(J3-A7-PadP$8)") (class "Default")
      (node (ref "J3") (pin "P$8") (pinfunction "A7_P$8") (pintype "bidirectional"))
    )
    (net (code "75") (name "unconnected-(J3-A8-PadP$10)") (class "Default")
      (node (ref "J3") (pin "P$10") (pinfunction "A8_P$10") (pintype "bidirectional"))
    )
    (net (code "76") (name "unconnected-(J3-B6-PadP$7)") (class "Default")
      (node (ref "J3") (pin "P$7") (pinfunction "B6_P$7") (pintype "bidirectional"))
    )
    (net (code "77") (name "unconnected-(J3-B7-PadP$5)") (class "Default")
      (node (ref "J3") (pin "P$5") (pinfunction "B7_P$5") (pintype "bidirectional"))
    )
    (net (code "78") (name "unconnected-(J3-B8-PadP$3)") (class "Default")
      (node (ref "J3") (pin "P$3") (pinfunction "B8_P$3") (pintype "bidirectional"))
    )
    (net (code "79") (name "unconnected-(J5-A6-PadP$6)") (class "Default")
      (node (ref "J5") (pin "P$6") (pinfunction "A6_P$6") (pintype "bidirectional"))
    )
    (net (code "80") (name "unconnected-(J5-A7-PadP$8)") (class "Default")
      (node (ref "J5") (pin "P$8") (pinfunction "A7_P$8") (pintype "bidirectional"))
    )
    (net (code "81") (name "unconnected-(J5-A8-PadP$10)") (class "Default")
      (node (ref "J5") (pin "P$10") (pinfunction "A8_P$10") (pintype "bidirectional"))
    )
    (net (code "82") (name "unconnected-(J5-B6-PadP$7)") (class "Default")
      (node (ref "J5") (pin "P$7") (pinfunction "B6_P$7") (pintype "bidirectional"))
    )
    (net (code "83") (name "unconnected-(J5-B7-PadP$5)") (class "Default")
      (node (ref "J5") (pin "P$5") (pinfunction "B7_P$5") (pintype "bidirectional"))
    )
    (net (code "84") (name "unconnected-(J5-B8-PadP$3)") (class "Default")
      (node (ref "J5") (pin "P$3") (pinfunction "B8_P$3") (pintype "bidirectional"))
    )
    (net (code "85") (name "unconnected-(U1-NC-Pad4)") (class "Default")
      (node (ref "U1") (pin "4") (pinfunction "NC_4") (pintype "bidirectional"))
    )
    (net (code "86") (name "unconnected-(U2-NC-Pad4)") (class "Default")
      (node (ref "U2") (pin "4") (pinfunction "NC_4") (pintype "bidirectional"))
    )
    (net (code "87") (name "unconnected-(U5-A_B_SIDE-Pad17)") (class "Default")
      (node (ref "U5") (pin "17") (pinfunction "A_B_SIDE_17") (pintype "bidirectional"))
    )
    (net (code "88") (name "unconnected-(U5-GPIO4-Pad16)") (class "Default")
      (node (ref "U5") (pin "16") (pinfunction "GPIO4_16") (pintype "bidirectional"))
    )
    (net (code "89") (name "unconnected-(U5-VCONN-Pad3)") (class "Default")
      (node (ref "U5") (pin "3") (pinfunction "VCONN_3") (pintype "bidirectional"))
    )
    (net (code "90") (name "unconnected-(U5-VSYS-Pad22)") (class "Default")
      (node (ref "U5") (pin "22") (pinfunction "VSYS_22") (pintype "bidirectional"))
    )
    (net (code "91") (name "unconnected-(U6-ALERT-Pad19)") (class "Default")
      (node (ref "U6") (pin "19") (pinfunction "ALERT_19") (pintype "bidirectional"))
    )
    (net (code "92") (name "unconnected-(U6-ATTACH-Pad11)") (class "Default")
      (node (ref "U6") (pin "11") (pinfunction "ATTACH_11") (pintype "bidirectional"))
    )
    (net (code "93") (name "unconnected-(U6-A_B_SIDE-Pad17)") (class "Default")
      (node (ref "U6") (pin "17") (pinfunction "A_B_SIDE_17") (pintype "bidirectional"))
    )
    (net (code "94") (name "unconnected-(U6-GPIO-Pad15)") (class "Default")
      (node (ref "U6") (pin "15") (pinfunction "GPIO_15") (pintype "bidirectional"))
    )
    (net (code "95") (name "unconnected-(U6-POWER_OK2-Pad20)") (class "Default")
      (node (ref "U6") (pin "20") (pinfunction "POWER_OK2_20") (pintype "bidirectional"))
    )
    (net (code "96") (name "unconnected-(U6-POWER_OK3-Pad14)") (class "Default")
      (node (ref "U6") (pin "14") (pinfunction "POWER_OK3_14") (pintype "bidirectional"))
    )
    (net (code "97") (name "unconnected-(U6-SCL-Pad7)") (class "Default")
      (node (ref "U6") (pin "7") (pinfunction "SCL_7") (pintype "bidirectional"))
    )
    (net (code "98") (name "unconnected-(U6-SDA-Pad8)") (class "Default")
      (node (ref "U6") (pin "8") (pinfunction "SDA_8") (pintype "bidirectional"))
    )
  )
)
